# Sensor_Shield_V2.net
KiCad netlist of a schematic drawn in Altium Designer
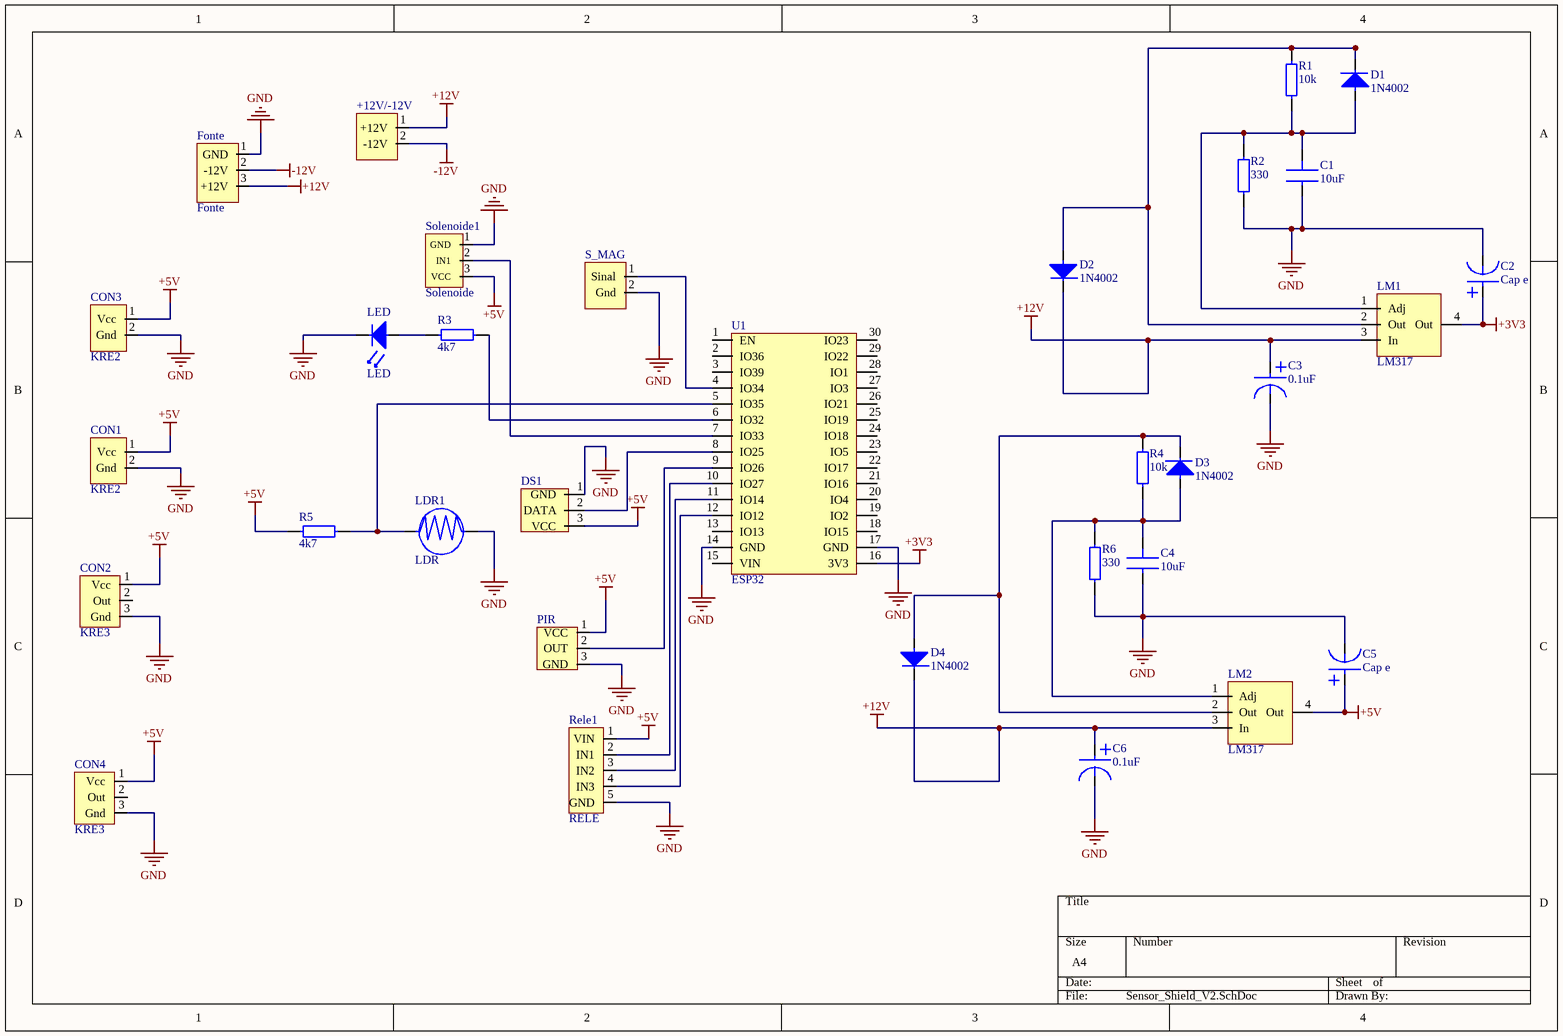
[diagram p0: Sensor_Shield_V2.SchDoc]

(export (version "E")
  (design (tool "Eeschema 10.0.6"))
  (components
    (comp (ref "+12V/-12V")
      (value "+12V/-12V")
      (footprint "KRE2")
      (libsource (lib "Sensor_Shield_V2") (part "+12V/-12V"))
    )
    (comp (ref "C1")
      (value "10uF")
      (footprint "C_ADJ")
      (description "C adj")
      (libsource (lib "Sensor_Shield_V2") (part "C10uF"))
    )
    (comp (ref "C2")
      (value "Cap e")
      (footprint "C_Eletrolitico")
      (libsource (lib "Sensor_Shield_V2") (part "C1.0uF"))
    )
    (comp (ref "C3")
      (value "0.1uF")
      (footprint "C_Tantalo")
      (description "Cap Tantalo")
      (libsource (lib "Sensor_Shield_V2") (part "C0.1uF"))
    )
    (comp (ref "C4")
      (value "10uF")
      (footprint "C_ADJ")
      (description "C adj")
      (libsource (lib "Sensor_Shield_V2") (part "C10uF"))
    )
    (comp (ref "C5")
      (value "Cap e")
      (footprint "C_Eletrolitico")
      (libsource (lib "Sensor_Shield_V2") (part "C1.0uF"))
    )
    (comp (ref "C6")
      (value "0.1uF")
      (footprint "C_Tantalo")
      (description "Cap Tantalo")
      (libsource (lib "Sensor_Shield_V2") (part "C0.1uF"))
    )
    (comp (ref "CON1") (value "KRE2") (footprint "KRE2") (libsource (lib "Sensor_Shield_V2") (part "KRE2")))
    (comp (ref "CON2") (value "KRE3") (footprint "KRE3") (libsource (lib "Sensor_Shield_V2") (part "KRE3")))
    (comp (ref "CON3") (value "KRE2") (footprint "KRE2") (libsource (lib "Sensor_Shield_V2") (part "KRE2")))
    (comp (ref "CON4") (value "KRE3") (footprint "KRE3") (libsource (lib "Sensor_Shield_V2") (part "KRE3")))
    (comp (ref "D1")
      (value "1N4002")
      (footprint "Do-214ac")
      (description "Diodo")
      (libsource (lib "Sensor_Shield_V2") (part "1N4002_smd"))
    )
    (comp (ref "D2")
      (value "1N4002")
      (footprint "Do-214ac")
      (description "Diodo")
      (libsource (lib "Sensor_Shield_V2") (part "1N4002_smd"))
    )
    (comp (ref "D3")
      (value "1N4002")
      (footprint "Do-214ac")
      (description "Diodo")
      (libsource (lib "Sensor_Shield_V2") (part "1N4002_smd"))
    )
    (comp (ref "D4")
      (value "1N4002")
      (footprint "Do-214ac")
      (description "Diodo")
      (libsource (lib "Sensor_Shield_V2") (part "1N4002_smd"))
    )
    (comp (ref "DS1")
      (value "Sensor Temperatura")
      (footprint "Ds18b20")
      (description "Ds18b20")
      (libsource (lib "Sensor_Shield_V2") (part "Ds18b20"))
    )
    (comp (ref "Fonte")
      (value "Fonte")
      (footprint "KRE3")
      (libsource (lib "Sensor_Shield_V2") (part "Fonte"))
    )
    (comp (ref "LDR1") (value "LDR") (footprint "LDR") (libsource (lib "Sensor_Shield_V2") (part "LDR")))
    (comp (ref "LED") (value "LED") (footprint "R0805") (libsource (lib "Sensor_Shield_V2") (part "LED")))
    (comp (ref "LM1") (value "LM317") (footprint "LM317") (libsource (lib "Sensor_Shield_V2") (part "LM317")))
    (comp (ref "LM2") (value "LM317") (footprint "LM317") (libsource (lib "Sensor_Shield_V2") (part "LM317")))
    (comp (ref "PIR") (value "Hc505") (footprint "PIR") (libsource (lib "Sensor_Shield_V2") (part "PIR505")))
    (comp (ref "R1")
      (value "10k")
      (footprint "R0805")
      (description "R0805")
      (libsource (lib "Sensor_Shield_V2") (part "R10k"))
    )
    (comp (ref "R2")
      (value "330")
      (footprint "R0805")
      (description "R0805")
      (libsource (lib "Sensor_Shield_V2") (part "R330"))
    )
    (comp (ref "R3")
      (value "4k7")
      (footprint "R0805")
      (description "R0805")
      (libsource (lib "Sensor_Shield_V2") (part "R4k7"))
    )
    (comp (ref "R4")
      (value "10k")
      (footprint "R0805")
      (description "R0805")
      (libsource (lib "Sensor_Shield_V2") (part "R10k"))
    )
    (comp (ref "R5")
      (value "4k7")
      (footprint "R0805")
      (description "R0805")
      (libsource (lib "Sensor_Shield_V2") (part "R4k7"))
    )
    (comp (ref "R6")
      (value "330")
      (footprint "R0805")
      (description "R0805")
      (libsource (lib "Sensor_Shield_V2") (part "R330"))
    )
    (comp (ref "Rele1")
      (value "RELE")
      (footprint "CON_5_TERM")
      (libsource (lib "Sensor_Shield_V2") (part "Relê"))
    )
    (comp (ref "Solenoide1")
      (value "Solenoide")
      (footprint "KRE3")
      (libsource (lib "Sensor_Shield_V2") (part "Solenoide"))
    )
    (comp (ref "S_MAG")
      (value "S_MAG")
      (footprint "KRE2")
      (libsource (lib "Sensor_Shield_V2") (part "S_MAG"))
    )
    (comp (ref "U1")
      (value "ESP32")
      (footprint "MODULO_ESP32")
      (description "Esp32")
      (libsource (lib "Sensor_Shield_V2") (part "ESP32"))
    )
  )
  (nets
    (net (code "1") (name "+3V3") (class "Default")
      (node (ref "C2") (pin "1") (pinfunction "1_1") (pintype "passive"))
      (node (ref "LM1") (pin "4") (pinfunction "Out_4") (pintype "passive"))
      (node (ref "U1") (pin "16") (pinfunction "3V3_16") (pintype "passive"))
    )
    (net (code "2") (name "+5V") (class "Default")
      (node (ref "C5") (pin "1") (pinfunction "1_1") (pintype "passive"))
      (node (ref "CON1") (pin "1") (pinfunction "Vcc_1") (pintype "passive"))
      (node (ref "CON2") (pin "1") (pinfunction "Vcc_1") (pintype "passive"))
      (node (ref "CON3") (pin "1") (pinfunction "Vcc_1") (pintype "passive"))
      (node (ref "CON4") (pin "1") (pinfunction "Vcc_1") (pintype "passive"))
      (node (ref "DS1") (pin "3") (pinfunction "VCC_3") (pintype "passive"))
      (node (ref "LM2") (pin "4") (pinfunction "Out_4") (pintype "passive"))
      (node (ref "PIR") (pin "1") (pinfunction "VCC_1") (pintype "passive"))
      (node (ref "R5") (pin "1") (pinfunction "1_1") (pintype "passive"))
      (node (ref "Rele1") (pin "1") (pinfunction "VIN_1") (pintype "passive"))
      (node (ref "Solenoide1") (pin "3") (pinfunction "VCC_3") (pintype "passive"))
    )
    (net (code "3") (name "+12V") (class "Default")
      (node (ref "+12V/-12V") (pin "1") (pinfunction "+12V_1") (pintype "passive"))
      (node (ref "C3") (pin "1") (pinfunction "1_1") (pintype "passive"))
      (node (ref "C6") (pin "1") (pinfunction "1_1") (pintype "passive"))
      (node (ref "D2") (pin "2") (pinfunction "2_2") (pintype "passive"))
      (node (ref "D4") (pin "2") (pinfunction "2_2") (pintype "passive"))
      (node (ref "Fonte") (pin "3") (pinfunction "+12V_3") (pintype "passive"))
      (node (ref "LM1") (pin "3") (pinfunction "In_3") (pintype "passive"))
      (node (ref "LM2") (pin "3") (pinfunction "In_3") (pintype "passive"))
    )
    (net (code "4") (name "-12V") (class "Default")
      (node (ref "+12V/-12V") (pin "2") (pinfunction "-12V_2") (pintype "passive"))
      (node (ref "Fonte") (pin "2") (pinfunction "-12V_2") (pintype "passive"))
    )
    (net (code "5") (name "GND") (class "Default")
      (node (ref "C1") (pin "1") (pinfunction "1_1") (pintype "passive"))
      (node (ref "C2") (pin "2") (pinfunction "2_2") (pintype "passive"))
      (node (ref "C3") (pin "2") (pinfunction "2_2") (pintype "passive"))
      (node (ref "C4") (pin "1") (pinfunction "1_1") (pintype "passive"))
      (node (ref "C5") (pin "2") (pinfunction "2_2") (pintype "passive"))
      (node (ref "C6") (pin "2") (pinfunction "2_2") (pintype "passive"))
      (node (ref "CON1") (pin "2") (pinfunction "Gnd_2") (pintype "passive"))
      (node (ref "CON2") (pin "3") (pinfunction "Gnd_3") (pintype "passive"))
      (node (ref "CON3") (pin "2") (pinfunction "Gnd_2") (pintype "passive"))
      (node (ref "CON4") (pin "3") (pinfunction "Gnd_3") (pintype "passive"))
      (node (ref "DS1") (pin "1") (pinfunction "GND_1") (pintype "passive"))
      (node (ref "Fonte") (pin "1") (pinfunction "GND_1") (pintype "passive"))
      (node (ref "LDR1") (pin "2") (pinfunction "2_2") (pintype "passive"))
      (node (ref "LED") (pin "2") (pinfunction "K_2") (pintype "passive"))
      (node (ref "PIR") (pin "3") (pinfunction "GND_3") (pintype "passive"))
      (node (ref "R2") (pin "1") (pinfunction "1_1") (pintype "passive"))
      (node (ref "R6") (pin "1") (pinfunction "1_1") (pintype "passive"))
      (node (ref "Rele1") (pin "5") (pinfunction "GND_5") (pintype "passive"))
      (node (ref "S_MAG") (pin "2") (pinfunction "Gnd_2") (pintype "passive"))
      (node (ref "Solenoide1") (pin "1") (pinfunction "GND_1") (pintype "passive"))
      (node (ref "U1") (pin "14") (pinfunction "GND_14") (pintype "passive"))
      (node (ref "U1") (pin "17") (pinfunction "GND_17") (pintype "passive"))
    )
    (net (code "6") (name "Net-(D1-Pad2)") (class "Default")
      (node (ref "D1") (pin "2") (pinfunction "2_2") (pintype "passive"))
      (node (ref "D2") (pin "1") (pinfunction "1_1") (pintype "passive"))
      (node (ref "LM1") (pin "2") (pinfunction "Out_2") (pintype "passive"))
      (node (ref "R1") (pin "2") (pinfunction "2_2") (pintype "passive"))
    )
    (net (code "7") (name "Net-(D3-Pad2)") (class "Default")
      (node (ref "D3") (pin "2") (pinfunction "2_2") (pintype "passive"))
      (node (ref "D4") (pin "1") (pinfunction "1_1") (pintype "passive"))
      (node (ref "LM2") (pin "2") (pinfunction "Out_2") (pintype "passive"))
      (node (ref "R4") (pin "2") (pinfunction "2_2") (pintype "passive"))
    )
    (net (code "8") (name "Net-(DS1-DATA)") (class "Default")
      (node (ref "DS1") (pin "2") (pinfunction "DATA_2") (pintype "passive"))
      (node (ref "U1") (pin "8") (pinfunction "IO25_8") (pintype "passive"))
    )
    (net (code "9") (name "Net-(LED-A)") (class "Default")
      (node (ref "LED") (pin "1") (pinfunction "A_1") (pintype "passive"))
      (node (ref "R3") (pin "1") (pinfunction "1_1") (pintype "passive"))
    )
    (net (code "10") (name "Net-(LM1-Adj)") (class "Default")
      (node (ref "C1") (pin "2") (pinfunction "2_2") (pintype "passive"))
      (node (ref "D1") (pin "1") (pinfunction "1_1") (pintype "passive"))
      (node (ref "LM1") (pin "1") (pinfunction "Adj_1") (pintype "passive"))
      (node (ref "R1") (pin "1") (pinfunction "1_1") (pintype "passive"))
      (node (ref "R2") (pin "2") (pinfunction "2_2") (pintype "passive"))
    )
    (net (code "11") (name "Net-(LM2-Adj)") (class "Default")
      (node (ref "C4") (pin "2") (pinfunction "2_2") (pintype "passive"))
      (node (ref "D3") (pin "1") (pinfunction "1_1") (pintype "passive"))
      (node (ref "LM2") (pin "1") (pinfunction "Adj_1") (pintype "passive"))
      (node (ref "R4") (pin "1") (pinfunction "1_1") (pintype "passive"))
      (node (ref "R6") (pin "2") (pinfunction "2_2") (pintype "passive"))
    )
    (net (code "12") (name "Net-(PIR-OUT)") (class "Default")
      (node (ref "PIR") (pin "2") (pinfunction "OUT_2") (pintype "passive"))
      (node (ref "U1") (pin "9") (pinfunction "IO26_9") (pintype "passive"))
    )
    (net (code "13") (name "Net-(Rele1-IN1)") (class "Default")
      (node (ref "Rele1") (pin "2") (pinfunction "IN1_2") (pintype "passive"))
      (node (ref "U1") (pin "10") (pinfunction "IO27_10") (pintype "passive"))
    )
    (net (code "14") (name "Net-(Rele1-IN2)") (class "Default")
      (node (ref "Rele1") (pin "3") (pinfunction "IN2_3") (pintype "passive"))
      (node (ref "U1") (pin "11") (pinfunction "IO14_11") (pintype "passive"))
    )
    (net (code "15") (name "Net-(Rele1-IN3)") (class "Default")
      (node (ref "Rele1") (pin "4") (pinfunction "IN3_4") (pintype "passive"))
      (node (ref "U1") (pin "12") (pinfunction "IO12_12") (pintype "passive"))
    )
    (net (code "16") (name "Net-(S_MAG-Sinal)") (class "Default")
      (node (ref "S_MAG") (pin "1") (pinfunction "Sinal_1") (pintype "passive"))
      (node (ref "U1") (pin "4") (pinfunction "IO34_4") (pintype "passive"))
    )
    (net (code "17") (name "Net-(Solenoide1-IN1)") (class "Default")
      (node (ref "Solenoide1") (pin "2") (pinfunction "IN1_2") (pintype "passive"))
      (node (ref "U1") (pin "7") (pinfunction "IO33_7") (pintype "passive"))
    )
    (net (code "18") (name "Net-(U1-IO32)") (class "Default")
      (node (ref "R3") (pin "2") (pinfunction "2_2") (pintype "passive"))
      (node (ref "U1") (pin "6") (pinfunction "IO32_6") (pintype "passive"))
    )
    (net (code "19") (name "Net-(U1-IO35)") (class "Default")
      (node (ref "LDR1") (pin "1") (pinfunction "1_1") (pintype "passive"))
      (node (ref "R5") (pin "2") (pinfunction "2_2") (pintype "passive"))
      (node (ref "U1") (pin "5") (pinfunction "IO35_5") (pintype "passive"))
    )
    (net (code "20") (name "unconnected-(CON2-Out-Pad2)") (class "Default")
      (node (ref "CON2") (pin "2") (pinfunction "Out_2") (pintype "passive"))
    )
    (net (code "21") (name "unconnected-(CON4-Out-Pad2)") (class "Default")
      (node (ref "CON4") (pin "2") (pinfunction "Out_2") (pintype "passive"))
    )
    (net (code "22") (name "unconnected-(U1-EN-Pad1)") (class "Default")
      (node (ref "U1") (pin "1") (pinfunction "EN_1") (pintype "passive"))
    )
    (net (code "23") (name "unconnected-(U1-IO1-Pad28)") (class "Default")
      (node (ref "U1") (pin "28") (pinfunction "IO1_28") (pintype "passive"))
    )
    (net (code "24") (name "unconnected-(U1-IO2-Pad19)") (class "Default")
      (node (ref "U1") (pin "19") (pinfunction "IO2_19") (pintype "passive"))
    )
    (net (code "25") (name "unconnected-(U1-IO3-Pad27)") (class "Default")
      (node (ref "U1") (pin "27") (pinfunction "IO3_27") (pintype "passive"))
    )
    (net (code "26") (name "unconnected-(U1-IO4-Pad20)") (class "Default")
      (node (ref "U1") (pin "20") (pinfunction "IO4_20") (pintype "passive"))
    )
    (net (code "27") (name "unconnected-(U1-IO5-Pad23)") (class "Default")
      (node (ref "U1") (pin "23") (pinfunction "IO5_23") (pintype "passive"))
    )
    (net (code "28") (name "unconnected-(U1-IO13-Pad13)") (class "Default")
      (node (ref "U1") (pin "13") (pinfunction "IO13_13") (pintype "passive"))
    )
    (net (code "29") (name "unconnected-(U1-IO15-Pad18)") (class "Default")
      (node (ref "U1") (pin "18") (pinfunction "IO15_18") (pintype "passive"))
    )
    (net (code "30") (name "unconnected-(U1-IO16-Pad21)") (class "Default")
      (node (ref "U1") (pin "21") (pinfunction "IO16_21") (pintype "passive"))
    )
    (net (code "31") (name "unconnected-(U1-IO17-Pad22)") (class "Default")
      (node (ref "U1") (pin "22") (pinfunction "IO17_22") (pintype "passive"))
    )
    (net (code "32") (name "unconnected-(U1-IO18-Pad24)") (class "Default")
      (node (ref "U1") (pin "24") (pinfunction "IO18_24") (pintype "passive"))
    )
    (net (code "33") (name "unconnected-(U1-IO19-Pad25)") (class "Default")
      (node (ref "U1") (pin "25") (pinfunction "IO19_25") (pintype "passive"))
    )
    (net (code "34") (name "unconnected-(U1-IO21-Pad26)") (class "Default")
      (node (ref "U1") (pin "26") (pinfunction "IO21_26") (pintype "passive"))
    )
    (net (code "35") (name "unconnected-(U1-IO22-Pad29)") (class "Default")
      (node (ref "U1") (pin "29") (pinfunction "IO22_29") (pintype "passive"))
    )
    (net (code "36") (name "unconnected-(U1-IO23-Pad30)") (class "Default")
      (node (ref "U1") (pin "30") (pinfunction "IO23_30") (pintype "passive"))
    )
    (net (code "37") (name "unconnected-(U1-IO36-Pad2)") (class "Default")
      (node (ref "U1") (pin "2") (pinfunction "IO36_2") (pintype "passive"))
    )
    (net (code "38") (name "unconnected-(U1-IO39-Pad3)") (class "Default")
      (node (ref "U1") (pin "3") (pinfunction "IO39_3") (pintype "passive"))
    )
    (net (code "39") (name "unconnected-(U1-VIN-Pad15)") (class "Default")
      (node (ref "U1") (pin "15") (pinfunction "VIN_15") (pintype "passive"))
    )
  )
)
